# DMMRectifier.net
KiCad netlist of a schematic drawn in EAGLE
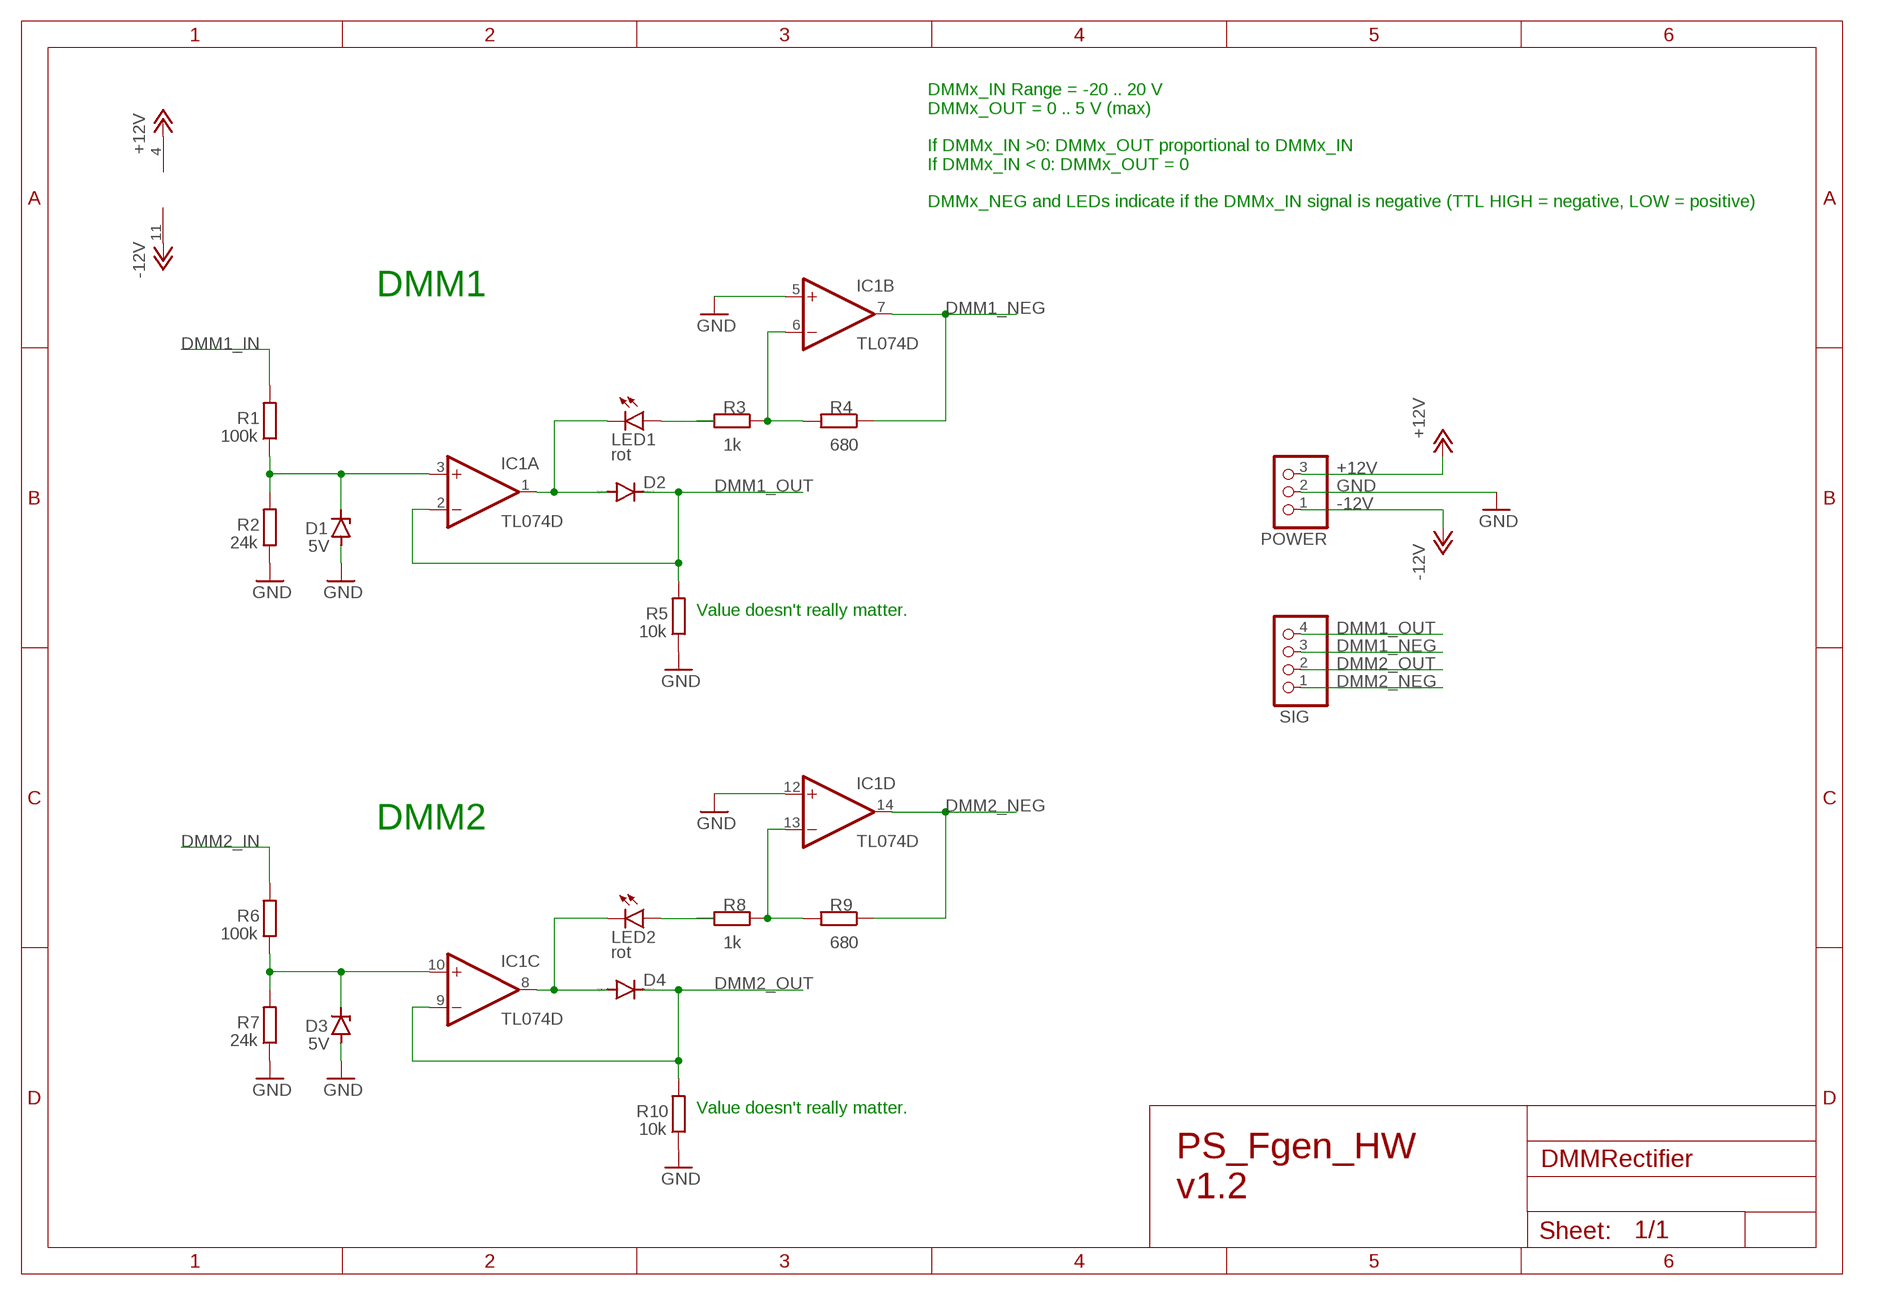
[diagram p0: schematic, sheet 1]

(export (version "E")
  (design (tool "Eeschema 10.0.6"))
  (components
    (comp (ref "D1")
      (value "5V")
      (footprint "eagle-import:SOD80C")
      (libsource (lib "eagle-import") (part "ZENER-DIODESOD80C"))
    )
    (comp (ref "D2")
      (value "DIODE-SOD80C")
      (footprint "eagle-import:SOD80C")
      (libsource (lib "eagle-import") (part "DIODE-SOD80C"))
    )
    (comp (ref "D3")
      (value "5V")
      (footprint "eagle-import:SOD80C")
      (libsource (lib "eagle-import") (part "ZENER-DIODESOD80C"))
    )
    (comp (ref "D4")
      (value "DIODE-SOD80C")
      (footprint "eagle-import:SOD80C")
      (libsource (lib "eagle-import") (part "DIODE-SOD80C"))
    )
    (comp (ref "IC1")
      (value "TL074D")
      (footprint "eagle-import:SO14")
      (fields (field (name "SPICEPREFIX") "I"))
      (libsource (lib "eagle-import") (part "TL074D"))
    )
    (comp (ref "LED1")
      (value "rot")
      (footprint "eagle-import:CHIPLED_0603")
      (libsource (lib "eagle-import") (part "LEDCHIPLED_0603"))
    )
    (comp (ref "LED2")
      (value "rot")
      (footprint "eagle-import:CHIPLED_0603")
      (libsource (lib "eagle-import") (part "LEDCHIPLED_0603"))
    )
    (comp (ref "POWER")
      (value "PINHD-1X3")
      (footprint "eagle-import:1X03")
      (libsource (lib "eagle-import") (part "PINHD-1X3"))
    )
    (comp (ref "R1")
      (value "100k")
      (footprint "eagle-import:R0805")
      (libsource (lib "eagle-import") (part "R-EU_R0805"))
    )
    (comp (ref "R2")
      (value "24k")
      (footprint "eagle-import:R0805")
      (libsource (lib "eagle-import") (part "R-EU_R0805"))
    )
    (comp (ref "R3")
      (value "1k")
      (footprint "eagle-import:R0805")
      (libsource (lib "eagle-import") (part "R-EU_R0805"))
    )
    (comp (ref "R4")
      (value "680")
      (footprint "eagle-import:R0805")
      (libsource (lib "eagle-import") (part "R-EU_R0805"))
    )
    (comp (ref "R5")
      (value "10k")
      (footprint "eagle-import:R0805")
      (libsource (lib "eagle-import") (part "R-EU_R0805"))
    )
    (comp (ref "R6")
      (value "100k")
      (footprint "eagle-import:R0805")
      (libsource (lib "eagle-import") (part "R-EU_R0805"))
    )
    (comp (ref "R7")
      (value "24k")
      (footprint "eagle-import:R0805")
      (libsource (lib "eagle-import") (part "R-EU_R0805"))
    )
    (comp (ref "R8")
      (value "1k")
      (footprint "eagle-import:R0805")
      (libsource (lib "eagle-import") (part "R-EU_R0805"))
    )
    (comp (ref "R9")
      (value "680")
      (footprint "eagle-import:R0805")
      (libsource (lib "eagle-import") (part "R-EU_R0805"))
    )
    (comp (ref "R10")
      (value "10k")
      (footprint "eagle-import:R0805")
      (libsource (lib "eagle-import") (part "R-EU_R0805"))
    )
    (comp (ref "SIG")
      (value "PINHD-1X4")
      (footprint "eagle-import:1X04")
      (libsource (lib "eagle-import") (part "PINHD-1X4"))
    )
  )
  (nets
    (net (code "1") (name "+12V") (class "Default")
      (node (ref "IC1") (pin "4") (pinfunction "V+_4") (pintype "power_in"))
      (node (ref "POWER") (pin "3") (pinfunction "3_3") (pintype "passive"))
    )
    (net (code "2") (name "-12V") (class "Default")
      (node (ref "IC1") (pin "11") (pinfunction "V-_11") (pintype "power_in"))
      (node (ref "POWER") (pin "1") (pinfunction "1_1") (pintype "passive"))
    )
    (net (code "3") (name "/DMM1_IN") (class "Default")
      (node (ref "R1") (pin "2") (pinfunction "2_2") (pintype "passive"))
    )
    (net (code "4") (name "/DMM1_NEG") (class "Default")
      (node (ref "IC1") (pin "7") (pinfunction "OUT_7") (pintype "output"))
      (node (ref "R4") (pin "1") (pinfunction "1_1") (pintype "passive"))
      (node (ref "SIG") (pin "3") (pinfunction "3_3") (pintype "passive"))
    )
    (net (code "5") (name "/DMM1_OUT") (class "Default")
      (node (ref "D2") (pin "C") (pinfunction "C_C") (pintype "passive"))
      (node (ref "IC1") (pin "2") (pinfunction "-IN_2") (pintype "input"))
      (node (ref "R5") (pin "2") (pinfunction "2_2") (pintype "passive"))
      (node (ref "SIG") (pin "4") (pinfunction "4_4") (pintype "passive"))
    )
    (net (code "6") (name "/DMM2_IN") (class "Default")
      (node (ref "R6") (pin "2") (pinfunction "2_2") (pintype "passive"))
    )
    (net (code "7") (name "/DMM2_NEG") (class "Default")
      (node (ref "IC1") (pin "14") (pinfunction "OUT_14") (pintype "output"))
      (node (ref "R9") (pin "1") (pinfunction "1_1") (pintype "passive"))
      (node (ref "SIG") (pin "1") (pinfunction "1_1") (pintype "passive"))
    )
    (net (code "8") (name "/DMM2_OUT") (class "Default")
      (node (ref "D4") (pin "C") (pinfunction "C_C") (pintype "passive"))
      (node (ref "IC1") (pin "9") (pinfunction "-IN_9") (pintype "input"))
      (node (ref "R10") (pin "2") (pinfunction "2_2") (pintype "passive"))
      (node (ref "SIG") (pin "2") (pinfunction "2_2") (pintype "passive"))
    )
    (net (code "9") (name "GND") (class "Default")
      (node (ref "D1") (pin "A") (pinfunction "A_A") (pintype "passive"))
      (node (ref "D3") (pin "A") (pinfunction "A_A") (pintype "passive"))
      (node (ref "IC1") (pin "12") (pinfunction "+IN_12") (pintype "input"))
      (node (ref "IC1") (pin "5") (pinfunction "+IN_5") (pintype "input"))
      (node (ref "POWER") (pin "2") (pinfunction "2_2") (pintype "passive"))
      (node (ref "R10") (pin "1") (pinfunction "1_1") (pintype "passive"))
      (node (ref "R2") (pin "1") (pinfunction "1_1") (pintype "passive"))
      (node (ref "R5") (pin "1") (pinfunction "1_1") (pintype "passive"))
      (node (ref "R7") (pin "1") (pinfunction "1_1") (pintype "passive"))
    )
    (net (code "10") (name "Net-(IC1A-+IN)") (class "Default")
      (node (ref "D1") (pin "C") (pinfunction "C_C") (pintype "passive"))
      (node (ref "IC1") (pin "3") (pinfunction "+IN_3") (pintype "input"))
      (node (ref "R1") (pin "1") (pinfunction "1_1") (pintype "passive"))
      (node (ref "R2") (pin "2") (pinfunction "2_2") (pintype "passive"))
    )
    (net (code "11") (name "Net-(IC1A-OUT)") (class "Default")
      (node (ref "D2") (pin "A") (pinfunction "A_A") (pintype "passive"))
      (node (ref "IC1") (pin "1") (pinfunction "OUT_1") (pintype "output"))
      (node (ref "LED1") (pin "C") (pinfunction "C_C") (pintype "passive"))
    )
    (net (code "12") (name "Net-(IC1B--IN)") (class "Default")
      (node (ref "IC1") (pin "6") (pinfunction "-IN_6") (pintype "input"))
      (node (ref "R3") (pin "1") (pinfunction "1_1") (pintype "passive"))
      (node (ref "R4") (pin "2") (pinfunction "2_2") (pintype "passive"))
    )
    (net (code "13") (name "Net-(IC1C-+IN)") (class "Default")
      (node (ref "D3") (pin "C") (pinfunction "C_C") (pintype "passive"))
      (node (ref "IC1") (pin "10") (pinfunction "+IN_10") (pintype "input"))
      (node (ref "R6") (pin "1") (pinfunction "1_1") (pintype "passive"))
      (node (ref "R7") (pin "2") (pinfunction "2_2") (pintype "passive"))
    )
    (net (code "14") (name "Net-(IC1C-OUT)") (class "Default")
      (node (ref "D4") (pin "A") (pinfunction "A_A") (pintype "passive"))
      (node (ref "IC1") (pin "8") (pinfunction "OUT_8") (pintype "output"))
      (node (ref "LED2") (pin "C") (pinfunction "C_C") (pintype "passive"))
    )
    (net (code "15") (name "Net-(IC1D--IN)") (class "Default")
      (node (ref "IC1") (pin "13") (pinfunction "-IN_13") (pintype "input"))
      (node (ref "R8") (pin "1") (pinfunction "1_1") (pintype "passive"))
      (node (ref "R9") (pin "2") (pinfunction "2_2") (pintype "passive"))
    )
    (net (code "16") (name "Net-(LED1-PadA)") (class "Default")
      (node (ref "LED1") (pin "A") (pinfunction "A_A") (pintype "passive"))
      (node (ref "R3") (pin "2") (pinfunction "2_2") (pintype "passive"))
    )
    (net (code "17") (name "Net-(LED2-PadA)") (class "Default")
      (node (ref "LED2") (pin "A") (pinfunction "A_A") (pintype "passive"))
      (node (ref "R8") (pin "2") (pinfunction "2_2") (pintype "passive"))
    )
  )
)
